# SmartIMU-BAT_Sch.net
KiCad netlist of a schematic drawn in Altium Designer
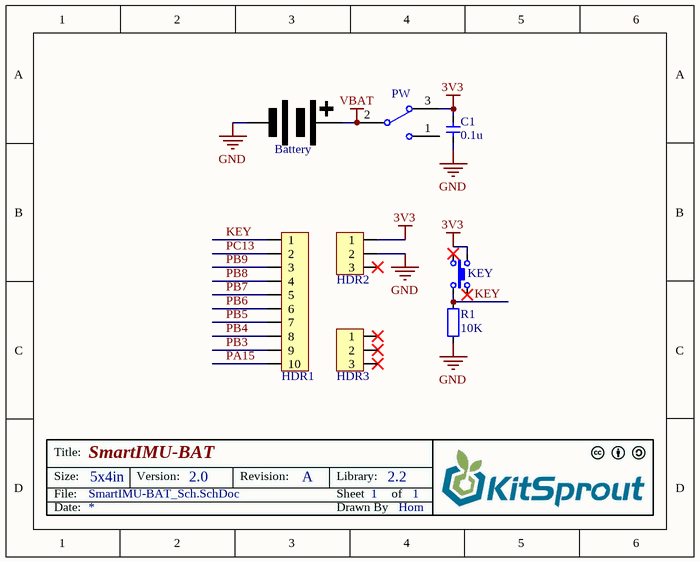
[diagram p0: SmartIMU-BAT_Sch.SchDoc]

(export (version "E")
  (design (tool "Eeschema 10.0.6"))
  (components
    (comp (ref "Battery")
      (value "Battery")
      (footprint "PCB_Battery:CR2032-1")
      (libsource (lib "SCH_Battery") (part "Battery"))
    )
    (comp (ref "C1")
      (value "0.1u")
      (footprint "PCB_PassiveCap:CAP_0603")
      (description "Capacitor")
      (fields (field (name "Comment") "Cap_0603"))
      (libsource (lib "SCH_Passive") (part "Cap_0603"))
    )
    (comp (ref "HDR1")
      (value "HDR1x10_2.54")
      (footprint "PCB_ConnectorHDR:HDR1X10_2.54_180F")
      (description "Header")
      (libsource (lib "SCH_ConnectorHDR") (part "HDR1x10_2.54"))
    )
    (comp (ref "HDR2")
      (value "HDR1x3_2.54")
      (footprint "PCB_ConnectorHDR:HDR1X3_2.54_180F")
      (description "Header")
      (libsource (lib "SCH_ConnectorHDR") (part "HDR1x3_2.54T"))
    )
    (comp (ref "HDR3")
      (value "HDR1x3_2.54")
      (footprint "PCB_ConnectorHDR:HDR1X3_2.54_180F")
      (description "Header")
      (libsource (lib "SCH_ConnectorHDR") (part "HDR1x3_2.54T"))
    )
    (comp (ref "KEY")
      (value "ButtonTACT")
      (footprint "PCB_Switch:ButtonTACT_3.5*3.55_90")
      (description "Button")
      (libsource (lib "SCH_Switch") (part "ButtonTACT"))
    )
    (comp (ref "PW")
      (value "SwitchSPDT_2.8x6.6_90")
      (footprint "PCB_Switch:SwitchSPDT_2.8X6.6_90")
      (description "Switch")
      (libsource (lib "SCH_Switch") (part "SwitchSPDT_2.8x6.6_90"))
    )
    (comp (ref "R1")
      (value "10K")
      (footprint "PCB_PassiveRes:RES_0603")
      (description "Resistor")
      (fields (field (name "Comment") "Res_0603"))
      (libsource (lib "SCH_Passive") (part "Res_0603"))
    )
  )
  (nets
    (net (code "1") (name "/KEY") (class "Default")
      (node (ref "HDR1") (pin "1") (pinfunction "1_1") (pintype "passive"))
      (node (ref "KEY") (pin "4") (pinfunction "4_4") (pintype "passive"))
      (node (ref "R1") (pin "2") (pinfunction "2_2") (pintype "passive"))
    )
    (net (code "2") (name "/PA15") (class "Default")
      (node (ref "HDR1") (pin "10") (pinfunction "10_10") (pintype "passive"))
    )
    (net (code "3") (name "/PB3") (class "Default")
      (node (ref "HDR1") (pin "9") (pinfunction "9_9") (pintype "passive"))
    )
    (net (code "4") (name "/PB4") (class "Default")
      (node (ref "HDR1") (pin "8") (pinfunction "8_8") (pintype "passive"))
    )
    (net (code "5") (name "/PB5") (class "Default")
      (node (ref "HDR1") (pin "7") (pinfunction "7_7") (pintype "passive"))
    )
    (net (code "6") (name "/PB6") (class "Default")
      (node (ref "HDR1") (pin "6") (pinfunction "6_6") (pintype "passive"))
    )
    (net (code "7") (name "/PB7") (class "Default")
      (node (ref "HDR1") (pin "5") (pinfunction "5_5") (pintype "passive"))
    )
    (net (code "8") (name "/PB8") (class "Default")
      (node (ref "HDR1") (pin "4") (pinfunction "4_4") (pintype "passive"))
    )
    (net (code "9") (name "/PB9") (class "Default")
      (node (ref "HDR1") (pin "3") (pinfunction "3_3") (pintype "passive"))
    )
    (net (code "10") (name "/PC13") (class "Default")
      (node (ref "HDR1") (pin "2") (pinfunction "2_2") (pintype "passive"))
    )
    (net (code "11") (name "3V3") (class "Default")
      (node (ref "C1") (pin "1") (pinfunction "1_1") (pintype "passive"))
      (node (ref "HDR2") (pin "1") (pinfunction "1_1") (pintype "passive"))
      (node (ref "KEY") (pin "1") (pinfunction "1_1") (pintype "passive"))
      (node (ref "PW") (pin "3") (pinfunction "3_3") (pintype "passive"))
    )
    (net (code "12") (name "GND") (class "Default")
      (node (ref "Battery") (pin "1") (pinfunction "-_1") (pintype "passive"))
      (node (ref "C1") (pin "2") (pinfunction "2_2") (pintype "passive"))
      (node (ref "HDR2") (pin "2") (pinfunction "2_2") (pintype "passive"))
      (node (ref "R1") (pin "1") (pinfunction "1_1") (pintype "passive"))
    )
    (net (code "13") (name "VBAT") (class "Default")
      (node (ref "Battery") (pin "2") (pinfunction "+_2") (pintype "passive"))
      (node (ref "PW") (pin "2") (pinfunction "2_2") (pintype "passive"))
    )
    (net (code "14") (name "unconnected-(HDR2-Pad3)") (class "Default")
      (node (ref "HDR2") (pin "3") (pinfunction "3_3") (pintype "passive+no_connect"))
    )
    (net (code "15") (name "unconnected-(HDR3-Pad1)") (class "Default")
      (node (ref "HDR3") (pin "1") (pinfunction "1_1") (pintype "passive+no_connect"))
    )
    (net (code "16") (name "unconnected-(HDR3-Pad2)") (class "Default")
      (node (ref "HDR3") (pin "2") (pinfunction "2_2") (pintype "passive+no_connect"))
    )
    (net (code "17") (name "unconnected-(HDR3-Pad3)") (class "Default")
      (node (ref "HDR3") (pin "3") (pinfunction "3_3") (pintype "passive+no_connect"))
    )
    (net (code "18") (name "unconnected-(KEY-Pad2)") (class "Default")
      (node (ref "KEY") (pin "2") (pinfunction "2_2") (pintype "passive+no_connect"))
    )
    (net (code "19") (name "unconnected-(KEY-Pad3)") (class "Default")
      (node (ref "KEY") (pin "3") (pinfunction "3_3") (pintype "passive+no_connect"))
    )
    (net (code "20") (name "unconnected-(PW-Pad1)") (class "Default")
      (node (ref "PW") (pin "1") (pinfunction "1_1") (pintype "passive"))
    )
  )
)
